# voltaje_regulator.net
KiCad netlist of a schematic drawn in Altium Designer
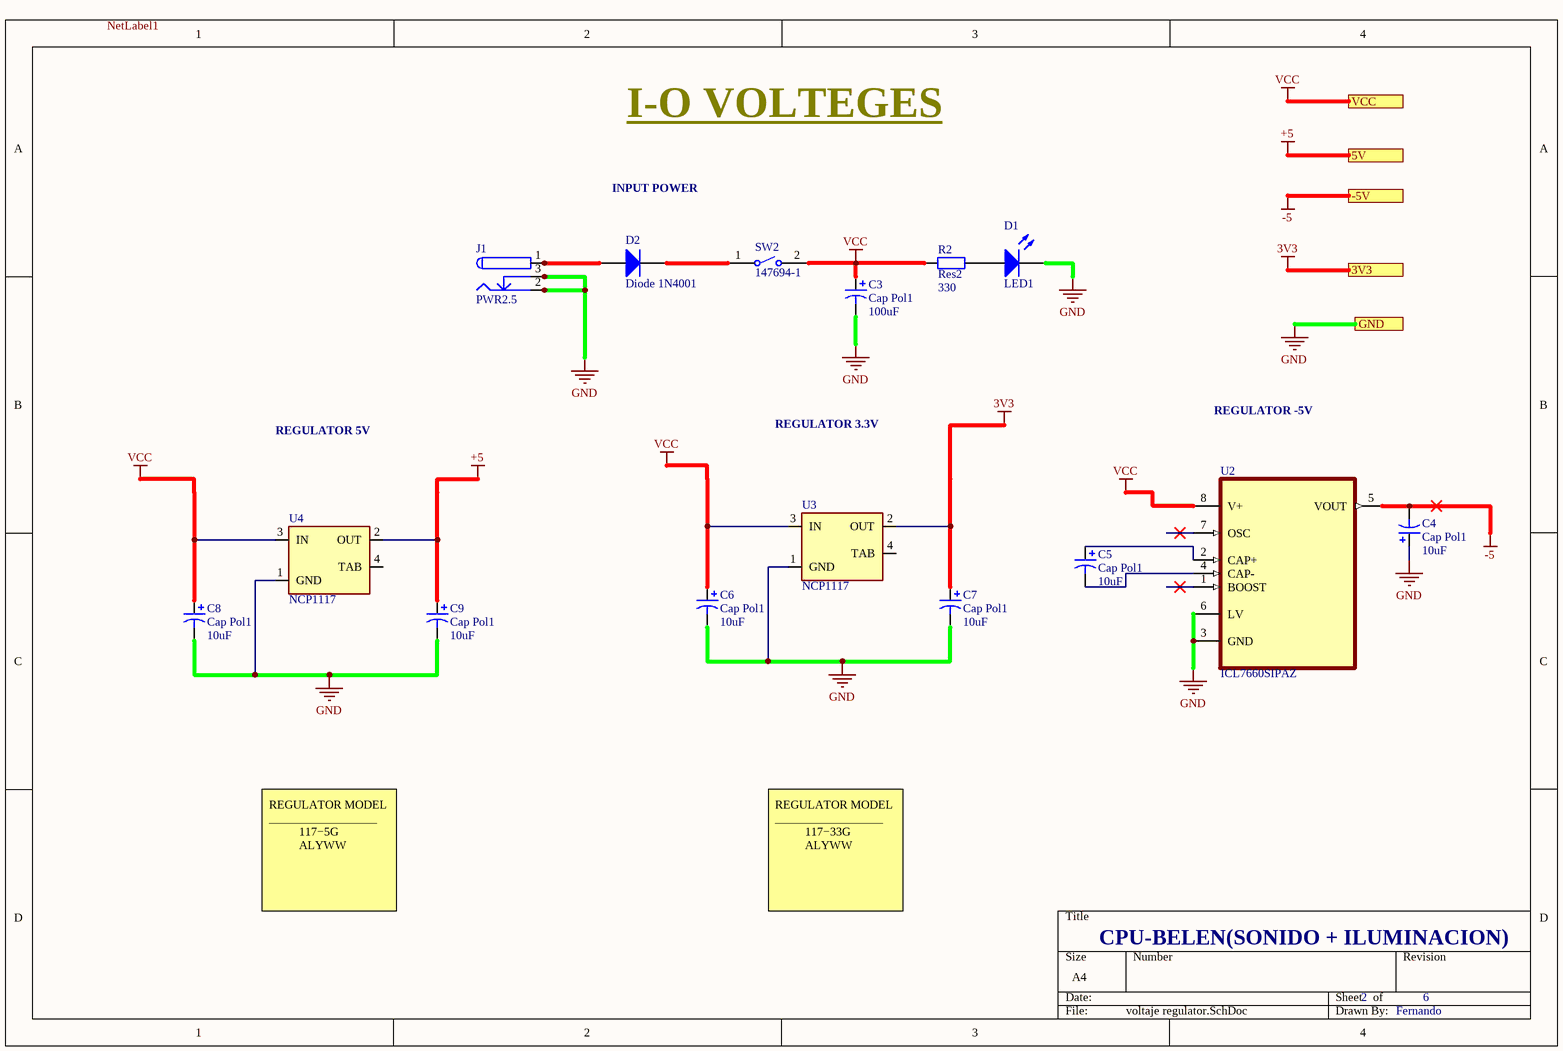
[diagram p0: voltaje regulator.SchDoc]

(export (version "E")
  (design (tool "Eeschema 10.0.6"))
  (components
    (comp (ref "C3")
      (value "Cap Pol1")
      (footprint "RB7.6-15")
      (description "Polarized Capacitor (Radial)")
      (fields (field (name "ALTIUM_VALUE") "100uF") (field (name "PUBLISHER") "Altium Limited"))
      (libsource (lib "Miscellaneous Devices") (part "Cap Pol1"))
    )
    (comp (ref "C4")
      (value "Cap Pol1")
      (footprint "RB7.6-15")
      (description "Polarized Capacitor (Radial)")
      (fields (field (name "ALTIUM_VALUE") "10uF") (field (name "PUBLISHER") "Altium Limited"))
      (libsource (lib "Miscellaneous Devices") (part "Cap Pol1"))
    )
    (comp (ref "C5")
      (value "Cap Pol1")
      (footprint "RB7.6-15")
      (description "Polarized Capacitor (Radial)")
      (fields (field (name "ALTIUM_VALUE") "10uF") (field (name "PUBLISHER") "Altium Limited"))
      (libsource (lib "Miscellaneous Devices") (part "Cap Pol1"))
    )
    (comp (ref "C6")
      (value "Cap Pol1")
      (footprint "RB7.6-15")
      (description "Polarized Capacitor (Radial)")
      (fields (field (name "ALTIUM_VALUE") "10uF") (field (name "PUBLISHER") "Altium Limited"))
      (libsource (lib "Miscellaneous Devices") (part "Cap Pol1"))
    )
    (comp (ref "C7")
      (value "Cap Pol1")
      (footprint "RB7.6-15")
      (description "Polarized Capacitor (Radial)")
      (fields (field (name "ALTIUM_VALUE") "10uF") (field (name "PUBLISHER") "Altium Limited"))
      (libsource (lib "Miscellaneous Devices") (part "Cap Pol1"))
    )
    (comp (ref "C8")
      (value "Cap Pol1")
      (footprint "RB7.6-15")
      (description "Polarized Capacitor (Radial)")
      (fields (field (name "ALTIUM_VALUE") "10uF") (field (name "PUBLISHER") "Altium Limited"))
      (libsource (lib "Miscellaneous Devices") (part "Cap Pol1"))
    )
    (comp (ref "C9")
      (value "Cap Pol1")
      (footprint "RB7.6-15")
      (description "Polarized Capacitor (Radial)")
      (fields (field (name "ALTIUM_VALUE") "10uF") (field (name "PUBLISHER") "Altium Limited"))
      (libsource (lib "Miscellaneous Devices") (part "Cap Pol1"))
    )
    (comp (ref "D1")
      (value "LED1")
      (footprint "LED-1")
      (description "Typical RED GaAs LED")
      (fields (field (name "PUBLISHER") "Altium Limited"))
      (libsource (lib "Miscellaneous Devices") (part "LED1"))
    )
    (comp (ref "D2")
      (value "Diode 1N4001")
      (footprint "DO-41")
      (description "1 Amp General Purpose Rectifier")
      (fields (field (name "PUBLISHER") "Altium Limited"))
      (libsource (lib "Miscellaneous Devices") (part "Diode 1N4001"))
    )
    (comp (ref "J1")
      (value "PWR2.5")
      (footprint "KLD-0202")
      (description "Low Voltage Power Supply Connector")
      (fields (field (name "PUBLISHER") "Altium Limited"))
      (libsource (lib "Miscellaneous Connectors") (part "PWR2.5"))
    )
    (comp (ref "R2")
      (value "Res2")
      (footprint "AXIAL-0.4")
      (description "Resistor")
      (fields (field (name "ALTIUM_VALUE") "330") (field (name "PUBLISHER") "Altium Limited"))
      (libsource (lib "Miscellaneous Devices") (part "Res2"))
    )
    (comp (ref "SW2")
      (value "147694-1")
      (footprint "TE_FSM8JRT")
      (description "Tactile Switch SPST-NO Top Actuated Through Hole")
      (fields (field (name "MF") "TE Connectivity"))
      (libsource (lib "147694-1") (part "147694-1"))
    )
    (comp (ref "U2")
      (value "ICL7660SIPAZ")
      (footprint "DIP254P762X533-8")
      (fields (field (name "MF") "Renesas Electronics"))
      (libsource (lib "ICL7660SIPAZ") (part "ICL7660SIPAZ"))
    )
    (comp (ref "U3")
      (value "NCP1117")
      (footprint "SOT223")
      (description "Linear Voltage Regulator IC 1 Output 1A DPAK")
      (fields (field (name "MF") "ON Semiconductor"))
      (libsource (lib "NCP1117") (part "NCP1117"))
    )
    (comp (ref "U4")
      (value "NCP1117")
      (footprint "SOT223")
      (description "Linear Voltage Regulator IC 1 Output 1A DPAK")
      (fields (field (name "MF") "ON Semiconductor"))
      (libsource (lib "NCP1117") (part "NCP1117"))
    )
  )
  (nets
    (net (code "1") (name "+5") (class "Default")
      (node (ref "C9") (pin "1") (pinfunction "1_1") (pintype "passive"))
      (node (ref "U4") (pin "2") (pinfunction "OUT_2") (pintype "bidirectional"))
    )
    (net (code "2") (name "-5") (class "Default")
      (node (ref "C4") (pin "2") (pinfunction "2_2") (pintype "passive"))
      (node (ref "U2") (pin "5") (pinfunction "VOUT_5") (pintype "output"))
    )
    (net (code "4") (name "3V3") (class "Default")
      (node (ref "C7") (pin "1") (pinfunction "1_1") (pintype "passive"))
      (node (ref "U3") (pin "2") (pinfunction "OUT_2") (pintype "bidirectional"))
    )
    (net (code "5") (name "GND") (class "Default")
      (node (ref "C3") (pin "2") (pinfunction "2_2") (pintype "passive"))
      (node (ref "C4") (pin "1") (pinfunction "1_1") (pintype "passive"))
      (node (ref "C6") (pin "2") (pinfunction "2_2") (pintype "passive"))
      (node (ref "C7") (pin "2") (pinfunction "2_2") (pintype "passive"))
      (node (ref "C8") (pin "2") (pinfunction "2_2") (pintype "passive"))
      (node (ref "C9") (pin "2") (pinfunction "2_2") (pintype "passive"))
      (node (ref "D1") (pin "2") (pinfunction "K_2") (pintype "passive"))
      (node (ref "J1") (pin "2") (pinfunction "2_2") (pintype "power_in"))
      (node (ref "J1") (pin "2A") (pinfunction "2A_2A") (pintype "power_in"))
      (node (ref "J1") (pin "2B") (pinfunction "2B_2B") (pintype "power_in"))
      (node (ref "J1") (pin "3") (pinfunction "3_3") (pintype "power_in"))
      (node (ref "J1") (pin "3A") (pinfunction "3A_3A") (pintype "power_in"))
      (node (ref "J1") (pin "3B") (pinfunction "3B_3B") (pintype "power_in"))
      (node (ref "U2") (pin "3") (pinfunction "GND_3") (pintype "passive"))
      (node (ref "U2") (pin "6") (pinfunction "LV_6") (pintype "passive"))
      (node (ref "U3") (pin "1") (pinfunction "GND_1") (pintype "bidirectional"))
      (node (ref "U4") (pin "1") (pinfunction "GND_1") (pintype "bidirectional"))
    )
    (net (code "6") (name "Net-(D1-A)") (class "Default")
      (node (ref "D1") (pin "1") (pinfunction "A_1") (pintype "passive"))
      (node (ref "R2") (pin "2") (pinfunction "2_2") (pintype "passive"))
    )
    (net (code "7") (name "Net-(D2-A)") (class "Default")
      (node (ref "D2") (pin "1") (pinfunction "A_1") (pintype "passive"))
      (node (ref "J1") (pin "1") (pinfunction "1_1") (pintype "power_in"))
      (node (ref "J1") (pin "1A") (pinfunction "1A_1A") (pintype "power_in"))
      (node (ref "J1") (pin "1B") (pinfunction "1B_1B") (pintype "power_in"))
    )
    (net (code "8") (name "Net-(D2-K)") (class "Default")
      (node (ref "D2") (pin "2") (pinfunction "K_2") (pintype "passive"))
      (node (ref "SW2") (pin "1") (pinfunction "1_1") (pintype "passive"))
    )
    (net (code "9") (name "Net-(U2-CAP+)") (class "Default")
      (node (ref "C5") (pin "1") (pinfunction "1_1") (pintype "passive"))
      (node (ref "U2") (pin "2") (pinfunction "CAP+_2") (pintype "input"))
    )
    (net (code "10") (name "Net-(U2-CAP-)") (class "Default")
      (node (ref "C5") (pin "2") (pinfunction "2_2") (pintype "passive"))
      (node (ref "U2") (pin "4") (pinfunction "CAP-_4") (pintype "input"))
    )
    (net (code "11") (name "VCC") (class "Default")
      (node (ref "C3") (pin "1") (pinfunction "1_1") (pintype "passive"))
      (node (ref "C6") (pin "1") (pinfunction "1_1") (pintype "passive"))
      (node (ref "C8") (pin "1") (pinfunction "1_1") (pintype "passive"))
      (node (ref "R2") (pin "1") (pinfunction "1_1") (pintype "passive"))
      (node (ref "SW2") (pin "2") (pinfunction "2_2") (pintype "passive"))
      (node (ref "U2") (pin "8") (pinfunction "V+_8") (pintype "power_in"))
      (node (ref "U3") (pin "3") (pinfunction "IN_3") (pintype "bidirectional"))
      (node (ref "U4") (pin "3") (pinfunction "IN_3") (pintype "bidirectional"))
    )
    (net (code "12") (name "unconnected-(U2-BOOST-Pad1)") (class "Default")
      (node (ref "U2") (pin "1") (pinfunction "BOOST_1") (pintype "input"))
    )
    (net (code "13") (name "unconnected-(U2-OSC-Pad7)") (class "Default")
      (node (ref "U2") (pin "7") (pinfunction "OSC_7") (pintype "input"))
    )
    (net (code "14") (name "unconnected-(U3-TAB-Pad4)") (class "Default")
      (node (ref "U3") (pin "4") (pinfunction "TAB_4") (pintype "bidirectional"))
    )
    (net (code "15") (name "unconnected-(U4-TAB-Pad4)") (class "Default")
      (node (ref "U4") (pin "4") (pinfunction "TAB_4") (pintype "bidirectional"))
    )
  )
)
